# Mem128_rev_A.net
KiCad netlist of a schematic drawn in EAGLE
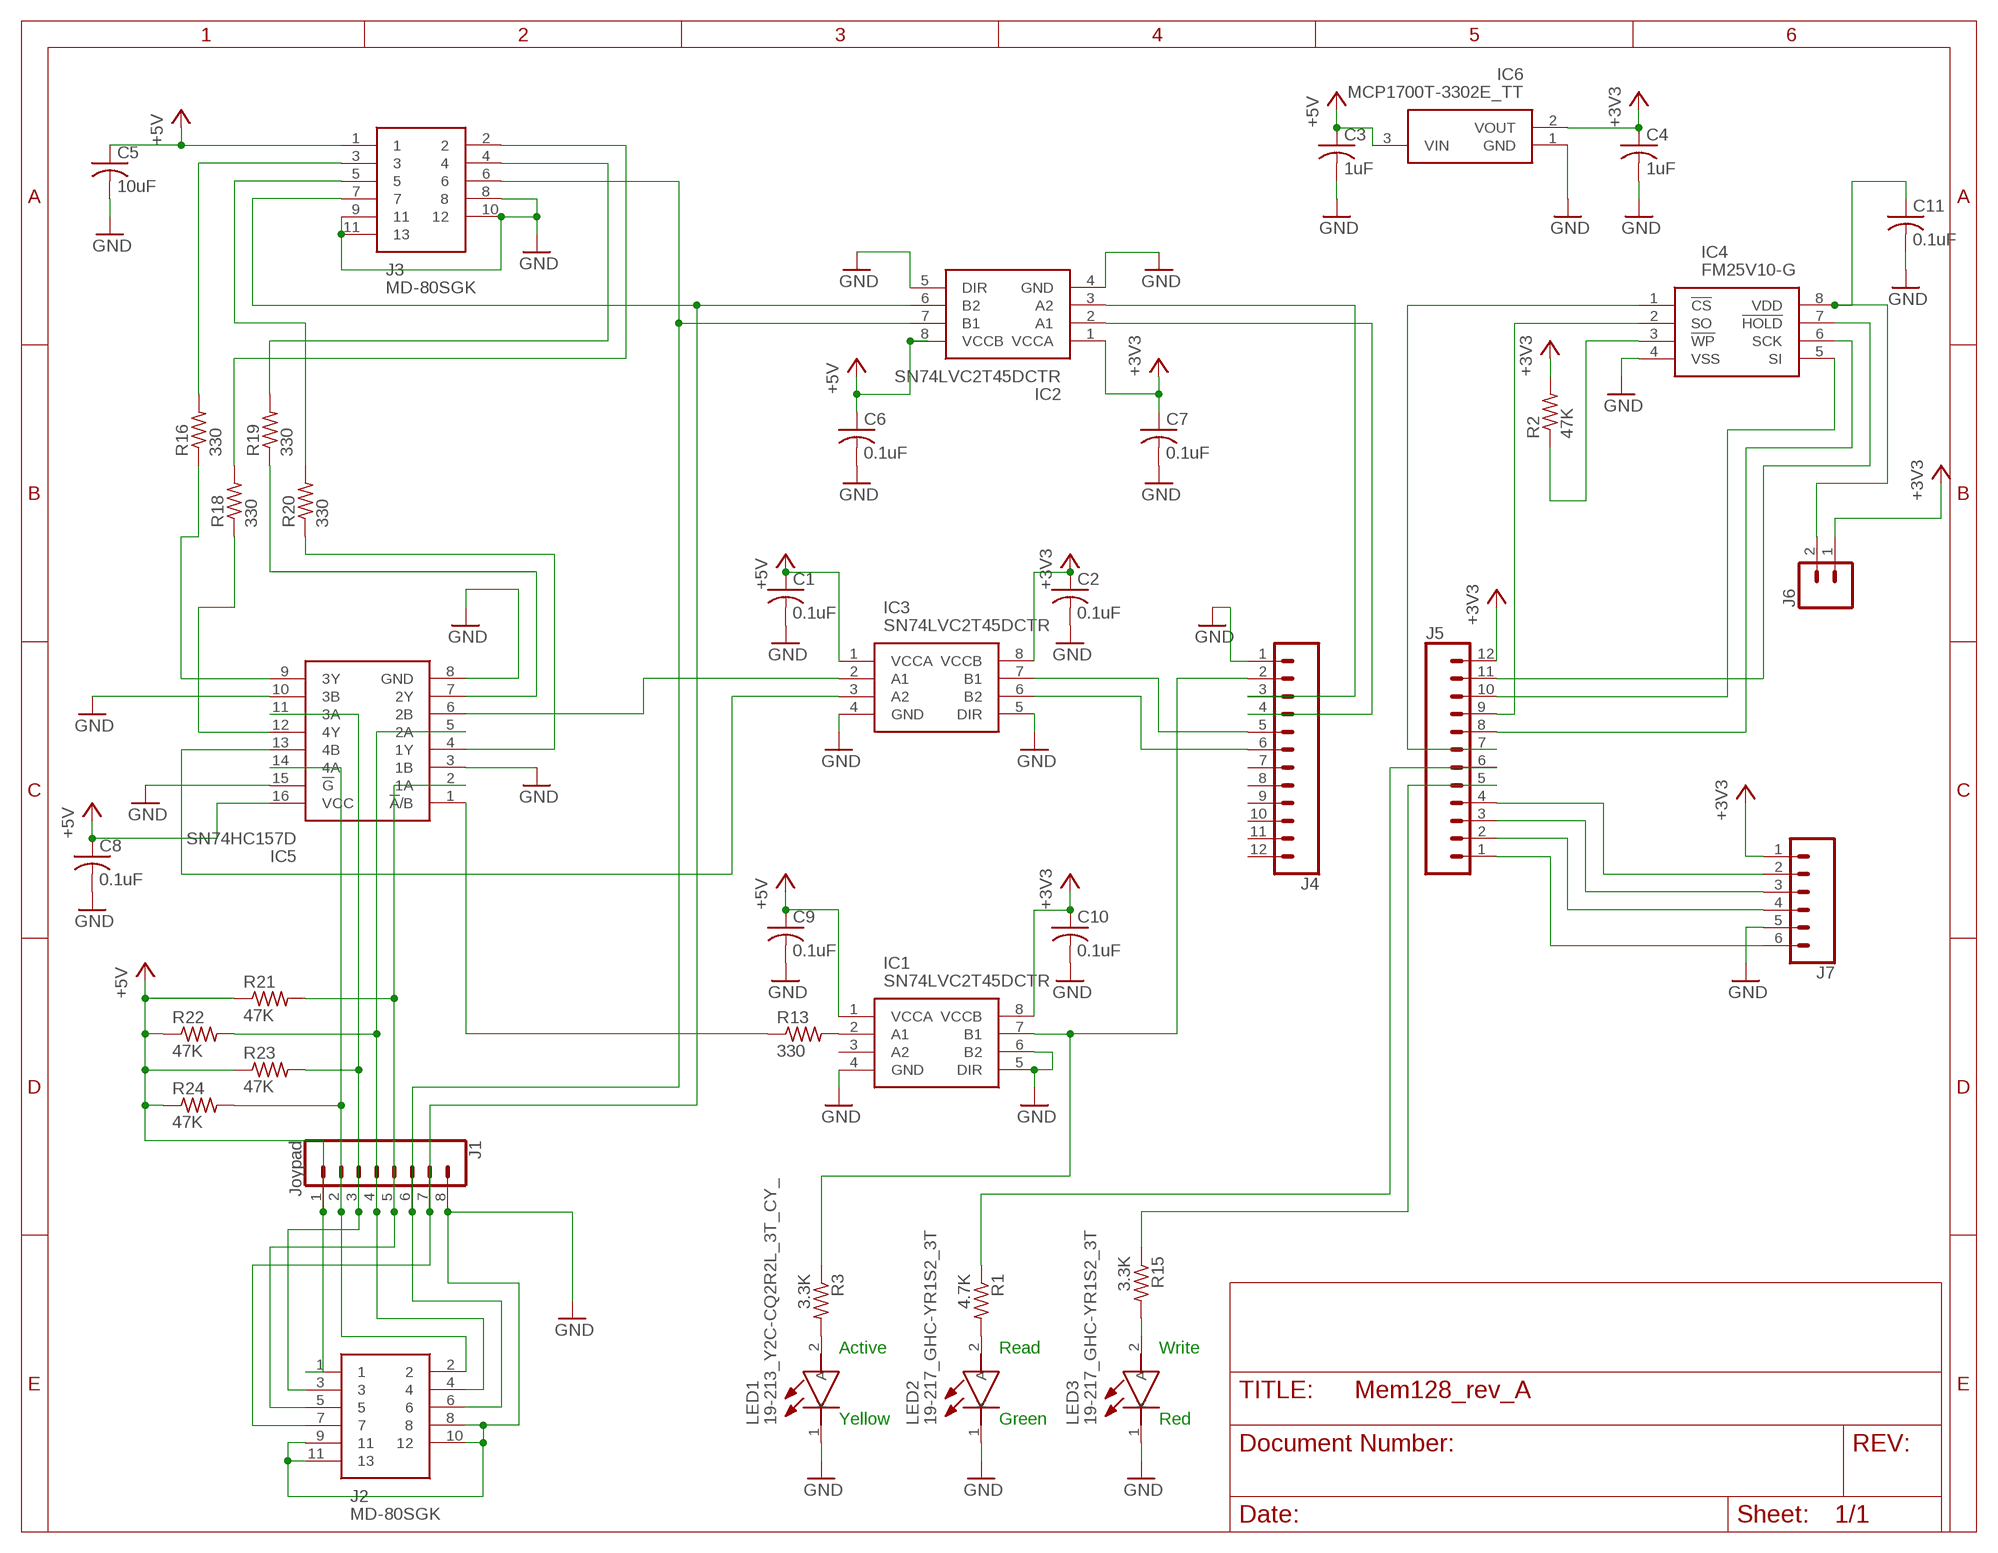
[diagram p0: schematic, sheet 1]

(export (version "E")
  (design (tool "Eeschema 10.0.6"))
  (components
    (comp (ref "C1")
      (value "0.1uF")
      (footprint "eagle-import:C0603")
      (libsource (lib "eagle-import") (part "C-USC0603"))
    )
    (comp (ref "C2")
      (value "0.1uF")
      (footprint "eagle-import:C0603")
      (libsource (lib "eagle-import") (part "C-USC0603"))
    )
    (comp (ref "C3")
      (value "1uF")
      (footprint "eagle-import:C0603")
      (libsource (lib "eagle-import") (part "C-USC0603"))
    )
    (comp (ref "C4")
      (value "1uF")
      (footprint "eagle-import:C0603")
      (libsource (lib "eagle-import") (part "C-USC0603"))
    )
    (comp (ref "C5")
      (value "10uF")
      (footprint "eagle-import:C0805")
      (libsource (lib "eagle-import") (part "C-USC0805"))
    )
    (comp (ref "C6")
      (value "0.1uF")
      (footprint "eagle-import:C0603")
      (libsource (lib "eagle-import") (part "C-USC0603"))
    )
    (comp (ref "C7")
      (value "0.1uF")
      (footprint "eagle-import:C0603")
      (libsource (lib "eagle-import") (part "C-USC0603"))
    )
    (comp (ref "C8")
      (value "0.1uF")
      (footprint "eagle-import:C0603")
      (libsource (lib "eagle-import") (part "C-USC0603"))
    )
    (comp (ref "C9")
      (value "0.1uF")
      (footprint "eagle-import:C0603")
      (libsource (lib "eagle-import") (part "C-USC0603"))
    )
    (comp (ref "C10")
      (value "0.1uF")
      (footprint "eagle-import:C0603")
      (libsource (lib "eagle-import") (part "C-USC0603"))
    )
    (comp (ref "C11")
      (value "0.1uF")
      (footprint "eagle-import:C0603")
      (libsource (lib "eagle-import") (part "C-USC0603"))
    )
    (comp (ref "IC1")
      (value "SN74LVC2T45DCTR")
      (footprint "eagle-import:SOP65P400X130-8N")
      (fields
        (field (name "MOUSER_PART_NUMBER") "595-SN74LVC2T45DCTR")
        (field (name "RS_PART_NUMBER") "9213022")
      )
      (libsource (lib "eagle-import") (part "SN74LVC2T45DCTR"))
    )
    (comp (ref "IC2")
      (value "SN74LVC2T45DCTR")
      (footprint "eagle-import:SOP65P400X130-8N")
      (fields
        (field (name "MOUSER_PART_NUMBER") "595-SN74LVC2T45DCTR")
        (field (name "RS_PART_NUMBER") "9213022")
      )
      (libsource (lib "eagle-import") (part "SN74LVC2T45DCTR"))
    )
    (comp (ref "IC3")
      (value "SN74LVC2T45DCTR")
      (footprint "eagle-import:SOP65P400X130-8N")
      (fields
        (field (name "MOUSER_PART_NUMBER") "595-SN74LVC2T45DCTR")
        (field (name "RS_PART_NUMBER") "9213022")
      )
      (libsource (lib "eagle-import") (part "SN74LVC2T45DCTR"))
    )
    (comp (ref "IC4")
      (value "FM25V10-G")
      (footprint "eagle-import:SOIC127P602X173-8N")
      (fields (field (name "MOUSER_PART_NUMBER") "877-FM25V10-G"))
      (libsource (lib "eagle-import") (part "FM25V10-G"))
    )
    (comp (ref "IC5")
      (value "SN74HC157D")
      (footprint "eagle-import:SOIC127P600X175-16N")
      (fields (field (name "MOUSER_PART_NUMBER") "595-SN74HC157D"))
      (libsource (lib "eagle-import") (part "SN74HC157D"))
    )
    (comp (ref "IC6")
      (value "MCP1700T-3302E_TT")
      (footprint "eagle-import:SOT95P237X112-3N")
      (fields
        (field (name "ARROW_PART_NUMBER") "MCP1700T-3302E/TT")
        (field (name "MOUSER_PART_NUMBER") "579-MCP1700T3302E/TT")
      )
      (libsource (lib "eagle-import") (part "MCP1700T-3302E_TT"))
    )
    (comp (ref "J1")
      (value "Joypad")
      (footprint "eagle-import:1X08")
      (libsource (lib "eagle-import") (part "CONN_08{dblquote}"))
    )
    (comp (ref "J2")
      (value "MD-80SGK")
      (footprint "eagle-import:MD80SGK")
      (fields (field (name "MOUSER_PART_NUMBER") "490-MD-80SGK"))
      (libsource (lib "eagle-import") (part "MD-80SGK"))
    )
    (comp (ref "J3")
      (value "MD-80SGK")
      (footprint "eagle-import:MD80SGK")
      (fields (field (name "MOUSER_PART_NUMBER") "490-MD-80SGK"))
      (libsource (lib "eagle-import") (part "MD-80SGK"))
    )
    (comp (ref "J4")
      (value "CONN_12")
      (footprint "eagle-import:1X12")
      (libsource (lib "eagle-import") (part "CONN_12"))
    )
    (comp (ref "J5")
      (value "CONN_12")
      (footprint "eagle-import:1X12")
      (libsource (lib "eagle-import") (part "CONN_12"))
    )
    (comp (ref "J6")
      (value "CONN_02")
      (footprint "eagle-import:1X02")
      (libsource (lib "eagle-import") (part "CONN_02"))
    )
    (comp (ref "J7")
      (value "CONN_06NO_SILK_FEMALE_PTH")
      (footprint "eagle-import:1X06_NO_SILK")
      (libsource (lib "eagle-import") (part "CONN_06NO_SILK_FEMALE_PTH"))
    )
    (comp (ref "LED1")
      (value "19-213_Y2C-CQ2R2L_3T_CY_")
      (footprint "eagle-import:LEDC1608X60N")
      (fields (field (name "ARROW_PART_NUMBER") "19-213/Y2C-CQ2R2L/3T(CY)"))
      (libsource (lib "eagle-import") (part "19-213_Y2C-CQ2R2L_3T_CY_"))
    )
    (comp (ref "LED2")
      (value "19-217_GHC-YR1S2_3T")
      (footprint "eagle-import:LEDC1608X50N")
      (fields
        (field (name "ARROW_PART_NUMBER") "19-217/GHC-YR1S2/3T")
        (field (name "MOUSER_PART_NUMBER") "638-19217GHCYR1S23T")
      )
      (libsource (lib "eagle-import") (part "19-217_GHC-YR1S2_3T"))
    )
    (comp (ref "LED3")
      (value "19-217_GHC-YR1S2_3T")
      (footprint "eagle-import:LEDC1608X50N")
      (fields
        (field (name "ARROW_PART_NUMBER") "19-217/GHC-YR1S2/3T")
        (field (name "MOUSER_PART_NUMBER") "638-19217GHCYR1S23T")
        (field (name "MANUFACTURER_NAME") "Hubei Kento")
        (field (name "MANUFACTURER_PART_NUMBER") "KT-0603R")
      )
      (libsource (lib "eagle-import") (part "19-217_GHC-YR1S2_3T"))
    )
    (comp (ref "R1")
      (value "4.7K")
      (footprint "eagle-import:R0603")
      (libsource (lib "eagle-import") (part "R-US_R0603"))
    )
    (comp (ref "R2")
      (value "47K")
      (footprint "eagle-import:R0603")
      (libsource (lib "eagle-import") (part "R-US_R0603"))
    )
    (comp (ref "R3")
      (value "3.3K")
      (footprint "eagle-import:R0603")
      (libsource (lib "eagle-import") (part "R-US_R0603"))
    )
    (comp (ref "R13")
      (value "330")
      (footprint "eagle-import:R0603")
      (libsource (lib "eagle-import") (part "R-US_R0603"))
    )
    (comp (ref "R15")
      (value "3.3K")
      (footprint "eagle-import:R0603")
      (libsource (lib "eagle-import") (part "R-US_R0603"))
    )
    (comp (ref "R16")
      (value "330")
      (footprint "eagle-import:R0603")
      (libsource (lib "eagle-import") (part "R-US_R0603"))
    )
    (comp (ref "R18")
      (value "330")
      (footprint "eagle-import:R0603")
      (libsource (lib "eagle-import") (part "R-US_R0603"))
    )
    (comp (ref "R19")
      (value "330")
      (footprint "eagle-import:R0603")
      (libsource (lib "eagle-import") (part "R-US_R0603"))
    )
    (comp (ref "R20")
      (value "330")
      (footprint "eagle-import:R0603")
      (libsource (lib "eagle-import") (part "R-US_R0603"))
    )
    (comp (ref "R21")
      (value "47K")
      (footprint "eagle-import:R0603")
      (libsource (lib "eagle-import") (part "R-US_R0603"))
    )
    (comp (ref "R22")
      (value "47K")
      (footprint "eagle-import:R0603")
      (libsource (lib "eagle-import") (part "R-US_R0603"))
    )
    (comp (ref "R23")
      (value "47K")
      (footprint "eagle-import:R0603")
      (libsource (lib "eagle-import") (part "R-US_R0603"))
    )
    (comp (ref "R24")
      (value "47K")
      (footprint "eagle-import:R0603")
      (libsource (lib "eagle-import") (part "R-US_R0603"))
    )
  )
  (nets
    (net (code "1") (name "+3V3") (class "Default")
      (node (ref "C10") (pin "1") (pinfunction "1_1") (pintype "passive"))
      (node (ref "C2") (pin "1") (pinfunction "1_1") (pintype "passive"))
      (node (ref "C4") (pin "1") (pinfunction "1_1") (pintype "passive"))
      (node (ref "C7") (pin "1") (pinfunction "1_1") (pintype "passive"))
      (node (ref "IC1") (pin "8") (pinfunction "VCCB_8") (pintype "power_in"))
      (node (ref "IC2") (pin "1") (pinfunction "VCCA_1") (pintype "power_in"))
      (node (ref "IC3") (pin "8") (pinfunction "VCCB_8") (pintype "power_in"))
      (node (ref "IC6") (pin "2") (pinfunction "VOUT_2") (pintype "bidirectional"))
      (node (ref "J5") (pin "12") (pinfunction "12_12") (pintype "passive"))
      (node (ref "J6") (pin "1") (pinfunction "1_1") (pintype "passive"))
      (node (ref "J7") (pin "1") (pinfunction "1_1") (pintype "passive"))
      (node (ref "R2") (pin "2") (pinfunction "2_2") (pintype "passive"))
    )
    (net (code "2") (name "+5V") (class "Default")
      (node (ref "C1") (pin "1") (pinfunction "1_1") (pintype "passive"))
      (node (ref "C3") (pin "1") (pinfunction "1_1") (pintype "passive"))
      (node (ref "C5") (pin "1") (pinfunction "1_1") (pintype "passive"))
      (node (ref "C6") (pin "1") (pinfunction "1_1") (pintype "passive"))
      (node (ref "C8") (pin "1") (pinfunction "1_1") (pintype "passive"))
      (node (ref "C9") (pin "1") (pinfunction "1_1") (pintype "passive"))
      (node (ref "IC1") (pin "1") (pinfunction "VCCA_1") (pintype "power_in"))
      (node (ref "IC2") (pin "8") (pinfunction "VCCB_8") (pintype "power_in"))
      (node (ref "IC3") (pin "1") (pinfunction "VCCA_1") (pintype "power_in"))
      (node (ref "IC5") (pin "16") (pinfunction "VCC_16") (pintype "bidirectional"))
      (node (ref "IC6") (pin "3") (pinfunction "VIN_3") (pintype "bidirectional"))
      (node (ref "J1") (pin "1") (pinfunction "1_1") (pintype "passive"))
      (node (ref "J2") (pin "1") (pinfunction "1_1") (pintype "bidirectional"))
      (node (ref "J3") (pin "1") (pinfunction "1_1") (pintype "bidirectional"))
      (node (ref "R21") (pin "1") (pinfunction "1_1") (pintype "passive"))
      (node (ref "R22") (pin "1") (pinfunction "1_1") (pintype "passive"))
      (node (ref "R23") (pin "1") (pinfunction "1_1") (pintype "passive"))
      (node (ref "R24") (pin "1") (pinfunction "1_1") (pintype "passive"))
    )
    (net (code "3") (name "GND") (class "Default")
      (node (ref "C1") (pin "2") (pinfunction "2_2") (pintype "passive"))
      (node (ref "C10") (pin "2") (pinfunction "2_2") (pintype "passive"))
      (node (ref "C11") (pin "2") (pinfunction "2_2") (pintype "passive"))
      (node (ref "C2") (pin "2") (pinfunction "2_2") (pintype "passive"))
      (node (ref "C3") (pin "2") (pinfunction "2_2") (pintype "passive"))
      (node (ref "C4") (pin "2") (pinfunction "2_2") (pintype "passive"))
      (node (ref "C5") (pin "2") (pinfunction "2_2") (pintype "passive"))
      (node (ref "C6") (pin "2") (pinfunction "2_2") (pintype "passive"))
      (node (ref "C7") (pin "2") (pinfunction "2_2") (pintype "passive"))
      (node (ref "C8") (pin "2") (pinfunction "2_2") (pintype "passive"))
      (node (ref "C9") (pin "2") (pinfunction "2_2") (pintype "passive"))
      (node (ref "IC1") (pin "4") (pinfunction "GND_4") (pintype "power_in"))
      (node (ref "IC1") (pin "5") (pinfunction "DIR_5") (pintype "bidirectional"))
      (node (ref "IC1") (pin "6") (pinfunction "B2_6") (pintype "bidirectional"))
      (node (ref "IC2") (pin "4") (pinfunction "GND_4") (pintype "power_in"))
      (node (ref "IC2") (pin "5") (pinfunction "DIR_5") (pintype "bidirectional"))
      (node (ref "IC3") (pin "4") (pinfunction "GND_4") (pintype "power_in"))
      (node (ref "IC3") (pin "5") (pinfunction "DIR_5") (pintype "bidirectional"))
      (node (ref "IC4") (pin "4") (pinfunction "VSS_4") (pintype "bidirectional"))
      (node (ref "IC5") (pin "10") (pinfunction "3B_10") (pintype "bidirectional"))
      (node (ref "IC5") (pin "15") (pinfunction "~{G}_15") (pintype "bidirectional"))
      (node (ref "IC5") (pin "3") (pinfunction "1B_3") (pintype "bidirectional"))
      (node (ref "IC5") (pin "8") (pinfunction "GND_8") (pintype "bidirectional"))
      (node (ref "IC6") (pin "1") (pinfunction "GND_1") (pintype "bidirectional"))
      (node (ref "J1") (pin "8") (pinfunction "8_8") (pintype "passive"))
      (node (ref "J2") (pin "10") (pinfunction "12_10") (pintype "bidirectional"))
      (node (ref "J2") (pin "11") (pinfunction "13_11") (pintype "bidirectional"))
      (node (ref "J2") (pin "8") (pinfunction "8_8") (pintype "bidirectional"))
      (node (ref "J2") (pin "9") (pinfunction "11_9") (pintype "bidirectional"))
      (node (ref "J3") (pin "10") (pinfunction "12_10") (pintype "bidirectional"))
      (node (ref "J3") (pin "11") (pinfunction "13_11") (pintype "bidirectional"))
      (node (ref "J3") (pin "8") (pinfunction "8_8") (pintype "bidirectional"))
      (node (ref "J3") (pin "9") (pinfunction "11_9") (pintype "bidirectional"))
      (node (ref "J4") (pin "1") (pinfunction "1_1") (pintype "passive"))
      (node (ref "J7") (pin "5") (pinfunction "5_5") (pintype "passive"))
      (node (ref "LED1") (pin "1") (pinfunction "K_1") (pintype "bidirectional"))
      (node (ref "LED2") (pin "1") (pinfunction "K_1") (pintype "bidirectional"))
      (node (ref "LED3") (pin "1") (pinfunction "K_1") (pintype "bidirectional"))
    )
    (net (code "4") (name "Net-(IC1-A1)") (class "Default")
      (node (ref "IC1") (pin "2") (pinfunction "A1_2") (pintype "bidirectional"))
      (node (ref "R13") (pin "2") (pinfunction "2_2") (pintype "passive"))
    )
    (net (code "5") (name "Net-(IC1-B1)") (class "Default")
      (node (ref "IC1") (pin "7") (pinfunction "B1_7") (pintype "bidirectional"))
      (node (ref "J4") (pin "2") (pinfunction "2_2") (pintype "passive"))
      (node (ref "R3") (pin "1") (pinfunction "1_1") (pintype "passive"))
    )
    (net (code "6") (name "Net-(IC2-A1)") (class "Default")
      (node (ref "IC2") (pin "2") (pinfunction "A1_2") (pintype "bidirectional"))
      (node (ref "J4") (pin "4") (pinfunction "4_4") (pintype "passive"))
    )
    (net (code "7") (name "Net-(IC2-A2)") (class "Default")
      (node (ref "IC2") (pin "3") (pinfunction "A2_3") (pintype "bidirectional"))
      (node (ref "J4") (pin "3") (pinfunction "3_3") (pintype "passive"))
    )
    (net (code "8") (name "Net-(IC2-B1)") (class "Default")
      (node (ref "IC2") (pin "7") (pinfunction "B1_7") (pintype "bidirectional"))
      (node (ref "J1") (pin "6") (pinfunction "6_6") (pintype "passive"))
      (node (ref "J2") (pin "6") (pinfunction "6_6") (pintype "bidirectional"))
      (node (ref "J3") (pin "6") (pinfunction "6_6") (pintype "bidirectional"))
    )
    (net (code "9") (name "Net-(IC2-B2)") (class "Default")
      (node (ref "IC2") (pin "6") (pinfunction "B2_6") (pintype "bidirectional"))
      (node (ref "J1") (pin "7") (pinfunction "7_7") (pintype "passive"))
      (node (ref "J2") (pin "7") (pinfunction "7_7") (pintype "bidirectional"))
      (node (ref "J3") (pin "7") (pinfunction "7_7") (pintype "bidirectional"))
    )
    (net (code "10") (name "Net-(IC3-A1)") (class "Default")
      (node (ref "IC3") (pin "2") (pinfunction "A1_2") (pintype "bidirectional"))
      (node (ref "IC5") (pin "6") (pinfunction "2B_6") (pintype "bidirectional"))
    )
    (net (code "11") (name "Net-(IC3-A2)") (class "Default")
      (node (ref "IC3") (pin "3") (pinfunction "A2_3") (pintype "bidirectional"))
      (node (ref "IC5") (pin "13") (pinfunction "4B_13") (pintype "bidirectional"))
    )
    (net (code "12") (name "Net-(IC3-B1)") (class "Default")
      (node (ref "IC3") (pin "7") (pinfunction "B1_7") (pintype "bidirectional"))
      (node (ref "J4") (pin "5") (pinfunction "5_5") (pintype "passive"))
    )
    (net (code "13") (name "Net-(IC3-B2)") (class "Default")
      (node (ref "IC3") (pin "6") (pinfunction "B2_6") (pintype "bidirectional"))
      (node (ref "J4") (pin "6") (pinfunction "6_6") (pintype "passive"))
    )
    (net (code "14") (name "Net-(IC4-SCK)") (class "Default")
      (node (ref "IC4") (pin "6") (pinfunction "SCK_6") (pintype "bidirectional"))
      (node (ref "J5") (pin "8") (pinfunction "8_8") (pintype "passive"))
    )
    (net (code "15") (name "Net-(IC4-SI)") (class "Default")
      (node (ref "IC4") (pin "5") (pinfunction "SI_5") (pintype "bidirectional"))
      (node (ref "J5") (pin "10") (pinfunction "10_10") (pintype "passive"))
    )
    (net (code "16") (name "Net-(IC4-SO)") (class "Default")
      (node (ref "IC4") (pin "2") (pinfunction "SO_2") (pintype "bidirectional"))
      (node (ref "J5") (pin "9") (pinfunction "9_9") (pintype "passive"))
    )
    (net (code "17") (name "Net-(IC4-VDD)") (class "Default")
      (node (ref "C11") (pin "1") (pinfunction "1_1") (pintype "passive"))
      (node (ref "IC4") (pin "8") (pinfunction "VDD_8") (pintype "bidirectional"))
      (node (ref "J6") (pin "2") (pinfunction "2_2") (pintype "passive"))
    )
    (net (code "18") (name "Net-(IC4-~{CS})") (class "Default")
      (node (ref "IC4") (pin "1") (pinfunction "~{CS}_1") (pintype "bidirectional"))
      (node (ref "J5") (pin "7") (pinfunction "7_7") (pintype "passive"))
    )
    (net (code "19") (name "Net-(IC4-~{HOLD})") (class "Default")
      (node (ref "IC4") (pin "7") (pinfunction "~{HOLD}_7") (pintype "bidirectional"))
      (node (ref "J5") (pin "11") (pinfunction "11_11") (pintype "passive"))
    )
    (net (code "20") (name "Net-(IC4-~{WP})") (class "Default")
      (node (ref "IC4") (pin "3") (pinfunction "~{WP}_3") (pintype "bidirectional"))
      (node (ref "R2") (pin "1") (pinfunction "1_1") (pintype "passive"))
    )
    (net (code "21") (name "Net-(IC5-1A)") (class "Default")
      (node (ref "IC5") (pin "2") (pinfunction "1A_2") (pintype "bidirectional"))
      (node (ref "J1") (pin "5") (pinfunction "5_5") (pintype "passive"))
      (node (ref "J2") (pin "5") (pinfunction "5_5") (pintype "bidirectional"))
      (node (ref "R21") (pin "2") (pinfunction "2_2") (pintype "passive"))
    )
    (net (code "22") (name "Net-(IC5-1Y)") (class "Default")
      (node (ref "IC5") (pin "4") (pinfunction "1Y_4") (pintype "bidirectional"))
      (node (ref "R20") (pin "1") (pinfunction "1_1") (pintype "passive"))
    )
    (net (code "23") (name "Net-(IC5-2A)") (class "Default")
      (node (ref "IC5") (pin "5") (pinfunction "2A_5") (pintype "bidirectional"))
      (node (ref "J1") (pin "4") (pinfunction "4_4") (pintype "passive"))
      (node (ref "J2") (pin "4") (pinfunction "4_4") (pintype "bidirectional"))
      (node (ref "R22") (pin "2") (pinfunction "2_2") (pintype "passive"))
    )
    (net (code "24") (name "Net-(IC5-2Y)") (class "Default")
      (node (ref "IC5") (pin "7") (pinfunction "2Y_7") (pintype "bidirectional"))
      (node (ref "R19") (pin "1") (pinfunction "1_1") (pintype "passive"))
    )
    (net (code "25") (name "Net-(IC5-3A)") (class "Default")
      (node (ref "IC5") (pin "11") (pinfunction "3A_11") (pintype "bidirectional"))
      (node (ref "J1") (pin "3") (pinfunction "3_3") (pintype "passive"))
      (node (ref "J2") (pin "3") (pinfunction "3_3") (pintype "bidirectional"))
      (node (ref "R23") (pin "2") (pinfunction "2_2") (pintype "passive"))
    )
    (net (code "26") (name "Net-(IC5-3Y)") (class "Default")
      (node (ref "IC5") (pin "9") (pinfunction "3Y_9") (pintype "bidirectional"))
      (node (ref "R16") (pin "1") (pinfunction "1_1") (pintype "passive"))
    )
    (net (code "27") (name "Net-(IC5-4A)") (class "Default")
      (node (ref "IC5") (pin "14") (pinfunction "4A_14") (pintype "bidirectional"))
      (node (ref "J1") (pin "2") (pinfunction "2_2") (pintype "passive"))
      (node (ref "J2") (pin "2") (pinfunction "2_2") (pintype "bidirectional"))
      (node (ref "R24") (pin "2") (pinfunction "2_2") (pintype "passive"))
    )
    (net (code "28") (name "Net-(IC5-4Y)") (class "Default")
      (node (ref "IC5") (pin "12") (pinfunction "4Y_12") (pintype "bidirectional"))
      (node (ref "R18") (pin "1") (pinfunction "1_1") (pintype "passive"))
    )
    (net (code "29") (name "Net-(IC5-~{A}{slash}B)") (class "Default")
      (node (ref "IC5") (pin "1") (pinfunction "~{A}/B_1") (pintype "bidirectional"))
      (node (ref "R13") (pin "1") (pinfunction "1_1") (pintype "passive"))
    )
    (net (code "30") (name "Net-(J3-Pad2)") (class "Default")
      (node (ref "J3") (pin "2") (pinfunction "2_2") (pintype "bidirectional"))
      (node (ref "R18") (pin "2") (pinfunction "2_2") (pintype "passive"))
    )
    (net (code "31") (name "Net-(J3-Pad3)") (class "Default")
      (node (ref "J3") (pin "3") (pinfunction "3_3") (pintype "bidirectional"))
      (node (ref "R16") (pin "2") (pinfunction "2_2") (pintype "passive"))
    )
    (net (code "32") (name "Net-(J3-Pad4)") (class "Default")
      (node (ref "J3") (pin "4") (pinfunction "4_4") (pintype "bidirectional"))
      (node (ref "R19") (pin "2") (pinfunction "2_2") (pintype "passive"))
    )
    (net (code "33") (name "Net-(J3-Pad5)") (class "Default")
      (node (ref "J3") (pin "5") (pinfunction "5_5") (pintype "bidirectional"))
      (node (ref "R20") (pin "2") (pinfunction "2_2") (pintype "passive"))
    )
    (net (code "34") (name "Net-(J5-Pad1)") (class "Default")
      (node (ref "J5") (pin "1") (pinfunction "1_1") (pintype "passive"))
      (node (ref "J7") (pin "6") (pinfunction "6_6") (pintype "passive"))
    )
    (net (code "35") (name "Net-(J5-Pad2)") (class "Default")
      (node (ref "J5") (pin "2") (pinfunction "2_2") (pintype "passive"))
      (node (ref "J7") (pin "4") (pinfunction "4_4") (pintype "passive"))
    )
    (net (code "36") (name "Net-(J5-Pad3)") (class "Default")
      (node (ref "J5") (pin "3") (pinfunction "3_3") (pintype "passive"))
      (node (ref "J7") (pin "3") (pinfunction "3_3") (pintype "passive"))
    )
    (net (code "37") (name "Net-(J5-Pad4)") (class "Default")
      (node (ref "J5") (pin "4") (pinfunction "4_4") (pintype "passive"))
      (node (ref "J7") (pin "2") (pinfunction "2_2") (pintype "passive"))
    )
    (net (code "38") (name "Net-(J5-Pad5)") (class "Default")
      (node (ref "J5") (pin "5") (pinfunction "5_5") (pintype "passive"))
      (node (ref "R15") (pin "1") (pinfunction "1_1") (pintype "passive"))
    )
    (net (code "39") (name "Net-(J5-Pad6)") (class "Default")
      (node (ref "J5") (pin "6") (pinfunction "6_6") (pintype "passive"))
      (node (ref "R1") (pin "1") (pinfunction "1_1") (pintype "passive"))
    )
    (net (code "40") (name "Net-(LED1-A)") (class "Default")
      (node (ref "LED1") (pin "2") (pinfunction "A_2") (pintype "bidirectional"))
      (node (ref "R3") (pin "2") (pinfunction "2_2") (pintype "passive"))
    )
    (net (code "41") (name "Net-(LED2-A)") (class "Default")
      (node (ref "LED2") (pin "2") (pinfunction "A_2") (pintype "bidirectional"))
      (node (ref "R1") (pin "2") (pinfunction "2_2") (pintype "passive"))
    )
    (net (code "42") (name "Net-(LED3-A)") (class "Default")
      (node (ref "LED3") (pin "2") (pinfunction "A_2") (pintype "bidirectional"))
      (node (ref "R15") (pin "2") (pinfunction "2_2") (pintype "passive"))
    )
    (net (code "43") (name "unconnected-(IC1-A2-Pad3)") (class "Default")
      (node (ref "IC1") (pin "3") (pinfunction "A2_3") (pintype "bidirectional"))
    )
    (net (code "44") (name "unconnected-(J4-Pad7)") (class "Default")
      (node (ref "J4") (pin "7") (pinfunction "7_7") (pintype "passive"))
    )
    (net (code "45") (name "unconnected-(J4-Pad8)") (class "Default")
      (node (ref "J4") (pin "8") (pinfunction "8_8") (pintype "passive"))
    )
    (net (code "46") (name "unconnected-(J4-Pad9)") (class "Default")
      (node (ref "J4") (pin "9") (pinfunction "9_9") (pintype "passive"))
    )
    (net (code "47") (name "unconnected-(J4-Pad10)") (class "Default")
      (node (ref "J4") (pin "10") (pinfunction "10_10") (pintype "passive"))
    )
    (net (code "48") (name "unconnected-(J4-Pad11)") (class "Default")
      (node (ref "J4") (pin "11") (pinfunction "11_11") (pintype "passive"))
    )
    (net (code "49") (name "unconnected-(J4-Pad12)") (class "Default")
      (node (ref "J4") (pin "12") (pinfunction "12_12") (pintype "passive"))
    )
  )
)
